# Preamp.net
KiCad netlist of a schematic drawn in Altium Designer
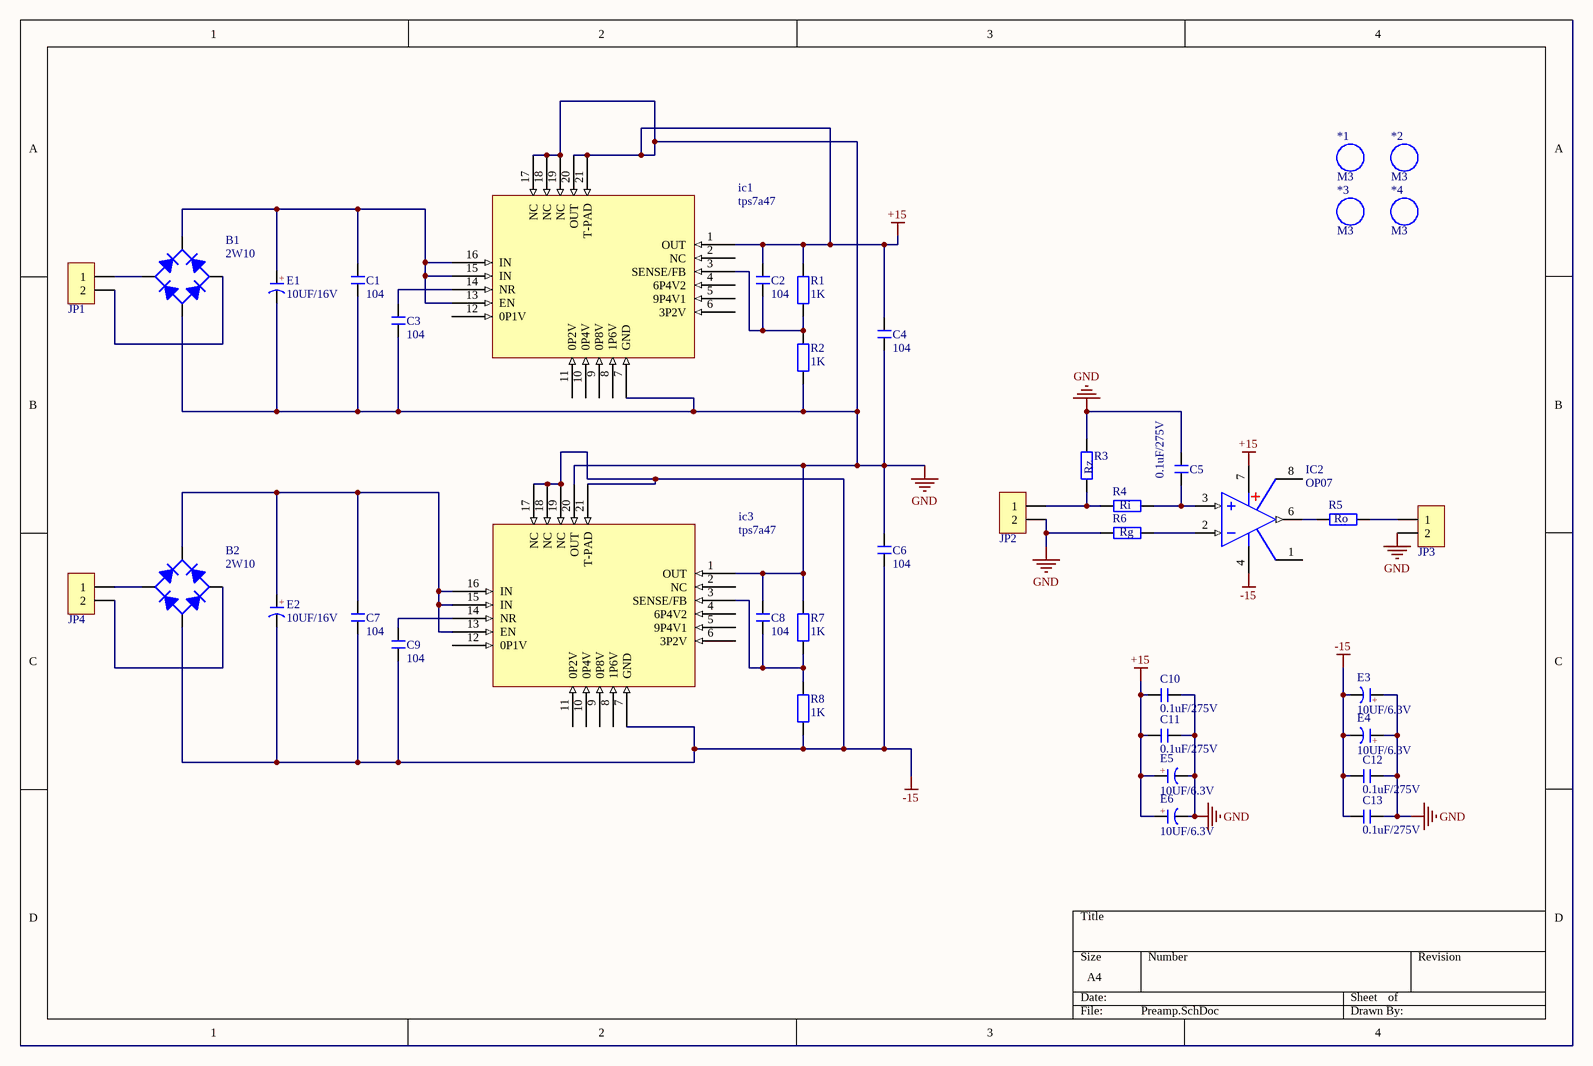
[diagram p0: Preamp.SchDoc]

(export (version "E")
  (design (tool "Eeschema 10.0.6"))
  (components
    (comp (ref "*1")
      (value "M3")
      (footprint "M3 125X300")
      (description "铜柱孔")
      (fields (field (name "版权归属") "源创客"))
      (libsource (lib "未分類") (part "M3"))
    )
    (comp (ref "*2")
      (value "M3")
      (footprint "M3 125X300")
      (description "铜柱孔")
      (fields (field (name "版权归属") "源创客"))
      (libsource (lib "未分類") (part "M3"))
    )
    (comp (ref "*3")
      (value "M3")
      (footprint "M3 125X300")
      (description "铜柱孔")
      (fields (field (name "版权归属") "源创客"))
      (libsource (lib "未分類") (part "M3"))
    )
    (comp (ref "*4")
      (value "M3")
      (footprint "M3 125X300")
      (description "铜柱孔")
      (fields (field (name "版权归属") "源创客"))
      (libsource (lib "未分類") (part "M3"))
    )
    (comp (ref "B1")
      (value "2W10")
      (footprint "RB-20")
      (description "1KV/2A淕霜")
      (libsource (lib "二極管-整流橋") (part "2W10"))
    )
    (comp (ref "B2")
      (value "2W10")
      (footprint "RB-20")
      (description "1KV/2A淕霜")
      (libsource (lib "二極管-整流橋") (part "2W10"))
    )
    (comp (ref "C1")
      (value "104")
      (footprint "C 0603")
      (description "拸憤俶泂萇")
      (libsource (lib "電阻-電容-電感") (part "C"))
    )
    (comp (ref "C2")
      (value "104")
      (footprint "C 0603")
      (description "拸憤俶泂萇")
      (libsource (lib "電阻-電容-電感") (part "C"))
    )
    (comp (ref "C3")
      (value "104")
      (footprint "C 0603")
      (description "拸憤俶泂萇")
      (libsource (lib "電阻-電容-電感") (part "C"))
    )
    (comp (ref "C4")
      (value "104")
      (footprint "C 0603")
      (description "拸憤俶泂萇")
      (libsource (lib "電阻-電容-電感") (part "C"))
    )
    (comp (ref "C5")
      (value "0.1uF/275V")
      (footprint "CBB-CL71")
      (description "CBB萇")
      (libsource (lib "電阻-電容-電感") (part "C-CBB"))
    )
    (comp (ref "C6")
      (value "104")
      (footprint "C 0603")
      (description "拸憤俶泂萇")
      (libsource (lib "電阻-電容-電感") (part "C"))
    )
    (comp (ref "C7")
      (value "104")
      (footprint "C 0603")
      (description "拸憤俶泂萇")
      (libsource (lib "電阻-電容-電感") (part "C"))
    )
    (comp (ref "C8")
      (value "104")
      (footprint "C 0603")
      (description "拸憤俶泂萇")
      (libsource (lib "電阻-電容-電感") (part "C"))
    )
    (comp (ref "C9")
      (value "104")
      (footprint "C 0603")
      (description "拸憤俶泂萇")
      (libsource (lib "電阻-電容-電感") (part "C"))
    )
    (comp (ref "C10")
      (value "0.1uF/275V")
      (footprint "CBB-CL71")
      (description "CBB萇")
      (libsource (lib "電阻-電容-電感") (part "C-CBB"))
    )
    (comp (ref "C11")
      (value "0.1uF/275V")
      (footprint "CBB-CL71")
      (description "CBB萇")
      (libsource (lib "電阻-電容-電感") (part "C-CBB"))
    )
    (comp (ref "C12")
      (value "0.1uF/275V")
      (footprint "CBB-CL71")
      (description "CBB萇")
      (libsource (lib "電阻-電容-電感") (part "C-CBB"))
    )
    (comp (ref "C13")
      (value "0.1uF/275V")
      (footprint "CBB-CL71")
      (description "CBB萇")
      (libsource (lib "電阻-電容-電感") (part "C-CBB"))
    )
    (comp (ref "E1")
      (value "10UF/16V")
      (footprint "CAP 7.5*18*35.5")
      (description "眻脣萇賤萇")
      (libsource (lib "電阻-電容-電感") (part "C-CAP"))
    )
    (comp (ref "E2")
      (value "10UF/16V")
      (footprint "CAP 7.5*18*35.5")
      (description "眻脣萇賤萇")
      (libsource (lib "電阻-電容-電感") (part "C-CAP"))
    )
    (comp (ref "E3")
      (value "10UF/6.3V")
      (footprint "CS 5.0*10*13 - C")
      (description "眻脣嘐怓萇")
      (libsource (lib "電阻-電容-電感") (part "C-CS"))
    )
    (comp (ref "E4")
      (value "10UF/6.3V")
      (footprint "CS 5.0*10*13 - C")
      (description "眻脣嘐怓萇")
      (libsource (lib "電阻-電容-電感") (part "C-CS"))
    )
    (comp (ref "E5")
      (value "10UF/6.3V")
      (footprint "CS 5.0*10*13 - C")
      (description "眻脣嘐怓萇")
      (libsource (lib "電阻-電容-電感") (part "C-CS"))
    )
    (comp (ref "E6")
      (value "10UF/6.3V")
      (footprint "CS 5.0*10*13 - C")
      (description "眻脣嘐怓萇")
      (libsource (lib "電阻-電容-電感") (part "C-CS"))
    )
    (comp (ref "ic1")
      (value "tps7a47")
      (footprint "QFN65P500X500X100_HS-21N")
      (description "TI RF LDO Voltage Regulator")
      (libsource (lib "vwvwbg") (part "tps7a47"))
    )
    (comp (ref "IC2")
      (value "OP07")
      (footprint "DIP8-300")
      (description "单路精密运放")
      (fields (field (name "版权归属") "源创客"))
      (libsource (lib "IC芯片") (part "OP07"))
    )
    (comp (ref "ic3")
      (value "tps7a47")
      (footprint "QFN65P500X500X100_HS-21N")
      (description "TI RF LDO Voltage Regulator")
      (libsource (lib "vwvwbg") (part "tps7a47"))
    )
    (comp (ref "JP1")
      (value "HDR-1X2")
      (footprint "KF2EDGK5.08-2P")
      (description "2P諉脣璃")
      (libsource (lib "") (part "Header 2_1"))
    )
    (comp (ref "JP2")
      (value "HDR-1X2")
      (footprint "KF2EDGK5.08-2P")
      (description "2P諉脣璃")
      (libsource (lib "") (part "Header 2_1"))
    )
    (comp (ref "JP3")
      (value "HDR-1X2")
      (footprint "KF2EDGK5.08-2P")
      (description "2P諉脣璃")
      (libsource (lib "接插件") (part "Header 2"))
    )
    (comp (ref "JP4")
      (value "HDR-1X2")
      (footprint "KF2EDGK5.08-2P")
      (description "2P諉脣璃")
      (libsource (lib "") (part "Header 2_1"))
    )
    (comp (ref "R1")
      (value "1K")
      (footprint "R 0805")
      (description "泂萇郯")
      (libsource (lib "電阻-電容-電感") (part "R"))
    )
    (comp (ref "R2")
      (value "1K")
      (footprint "R 0805")
      (description "泂萇郯")
      (libsource (lib "電阻-電容-電感") (part "R"))
    )
    (comp (ref "R3")
      (value "Rz")
      (footprint "RS 1/2W")
      (description "眻脣伎遠萇郯")
      (libsource (lib "電阻-電容-電感") (part "R-CRR"))
    )
    (comp (ref "R4")
      (value "Ri")
      (footprint "RS 1/2W")
      (description "眻脣伎遠萇郯")
      (libsource (lib "電阻-電容-電感") (part "R-CRR"))
    )
    (comp (ref "R5") (value "Ro") (footprint "RS 1/2W") (libsource (lib "電阻-電容-電感") (part "R-CRR")))
    (comp (ref "R6")
      (value "Rg")
      (footprint "RS 1/2W")
      (description "眻脣伎遠萇郯")
      (libsource (lib "電阻-電容-電感") (part "R-CRR"))
    )
    (comp (ref "R7")
      (value "1K")
      (footprint "R 0805")
      (description "泂萇郯")
      (libsource (lib "電阻-電容-電感") (part "R"))
    )
    (comp (ref "R8")
      (value "1K")
      (footprint "R 0805")
      (description "泂萇郯")
      (libsource (lib "電阻-電容-電感") (part "R"))
    )
  )
  (nets
    (net (code "1") (name "+15") (class "Default")
      (node (ref "B1") (pin "DC-") (pinfunction "DC-_DC-") (pintype "passive"))
      (node (ref "C1") (pin "1") (pinfunction "1_1") (pintype "passive"))
      (node (ref "C10") (pin "1") (pinfunction "1_1") (pintype "passive"))
      (node (ref "C10") (pin "2") (pinfunction "2_2") (pintype "passive"))
      (node (ref "C11") (pin "1") (pinfunction "1_1") (pintype "passive"))
      (node (ref "C11") (pin "2") (pinfunction "2_2") (pintype "passive"))
      (node (ref "C12") (pin "2") (pinfunction "2_2") (pintype "passive"))
      (node (ref "C13") (pin "2") (pinfunction "2_2") (pintype "passive"))
      (node (ref "C2") (pin "2") (pinfunction "2_2") (pintype "passive"))
      (node (ref "C3") (pin "1") (pinfunction "1_1") (pintype "passive"))
      (node (ref "C4") (pin "1") (pinfunction "1_1") (pintype "passive"))
      (node (ref "C4") (pin "2") (pinfunction "2_2") (pintype "passive"))
      (node (ref "C5") (pin "2") (pinfunction "2_2") (pintype "passive"))
      (node (ref "C6") (pin "2") (pinfunction "2_2") (pintype "passive"))
      (node (ref "C8") (pin "2") (pinfunction "2_2") (pintype "passive"))
      (node (ref "E1") (pin "2") (pinfunction "K_2") (pintype "passive"))
      (node (ref "E3") (pin "1") (pinfunction "A_1") (pintype "passive"))
      (node (ref "E4") (pin "1") (pinfunction "A_1") (pintype "passive"))
      (node (ref "E5") (pin "1") (pinfunction "A_1") (pintype "passive"))
      (node (ref "E5") (pin "2") (pinfunction "K_2") (pintype "passive"))
      (node (ref "E6") (pin "1") (pinfunction "A_1") (pintype "passive"))
      (node (ref "E6") (pin "2") (pinfunction "K_2") (pintype "passive"))
      (node (ref "IC2") (pin "7") (pinfunction "V+_7") (pintype "power_in"))
      (node (ref "JP2") (pin "2") (pinfunction "2_2") (pintype "passive"))
      (node (ref "JP3") (pin "2") (pinfunction "2_2") (pintype "passive"))
      (node (ref "R1") (pin "2") (pinfunction "2_2") (pintype "passive"))
      (node (ref "R2") (pin "1") (pinfunction "1_1") (pintype "passive"))
      (node (ref "R3") (pin "2") (pinfunction "2_2") (pintype "passive"))
      (node (ref "R6") (pin "1") (pinfunction "1_1") (pintype "passive"))
      (node (ref "R7") (pin "2") (pinfunction "2_2") (pintype "passive"))
      (node (ref "ic1") (pin "1") (pinfunction "OUT_1") (pintype "input"))
      (node (ref "ic1") (pin "17") (pinfunction "NC_17") (pintype "input"))
      (node (ref "ic1") (pin "18") (pinfunction "NC_18") (pintype "input"))
      (node (ref "ic1") (pin "19") (pinfunction "NC_19") (pintype "input"))
      (node (ref "ic1") (pin "20") (pinfunction "OUT_20") (pintype "input"))
      (node (ref "ic1") (pin "21") (pinfunction "T-PAD_21") (pintype "input"))
      (node (ref "ic1") (pin "7") (pinfunction "GND_7") (pintype "input"))
      (node (ref "ic3") (pin "1") (pinfunction "OUT_1") (pintype "input"))
      (node (ref "ic3") (pin "20") (pinfunction "OUT_20") (pintype "input"))
    )
    (net (code "2") (name "-15") (class "Default")
      (node (ref "B2") (pin "DC-") (pinfunction "DC-_DC-") (pintype "passive"))
      (node (ref "C12") (pin "1") (pinfunction "1_1") (pintype "passive"))
      (node (ref "C13") (pin "1") (pinfunction "1_1") (pintype "passive"))
      (node (ref "C6") (pin "1") (pinfunction "1_1") (pintype "passive"))
      (node (ref "C7") (pin "1") (pinfunction "1_1") (pintype "passive"))
      (node (ref "C9") (pin "1") (pinfunction "1_1") (pintype "passive"))
      (node (ref "E2") (pin "2") (pinfunction "K_2") (pintype "passive"))
      (node (ref "E3") (pin "2") (pinfunction "K_2") (pintype "passive"))
      (node (ref "E4") (pin "2") (pinfunction "K_2") (pintype "passive"))
      (node (ref "IC2") (pin "4") (pinfunction "V-_4") (pintype "power_in"))
      (node (ref "R8") (pin "1") (pinfunction "1_1") (pintype "passive"))
      (node (ref "ic3") (pin "17") (pinfunction "NC_17") (pintype "input"))
      (node (ref "ic3") (pin "18") (pinfunction "NC_18") (pintype "input"))
      (node (ref "ic3") (pin "19") (pinfunction "NC_19") (pintype "input"))
      (node (ref "ic3") (pin "21") (pinfunction "T-PAD_21") (pintype "input"))
      (node (ref "ic3") (pin "7") (pinfunction "GND_7") (pintype "input"))
    )
    (net (code "3") (name "Net-(B1-PadAC1)") (class "Default")
      (node (ref "B1") (pin "AC1") (pinfunction "AC1_AC1") (pintype "passive"))
      (node (ref "JP1") (pin "1") (pinfunction "1_1") (pintype "passive"))
    )
    (net (code "4") (name "Net-(B1-PadAC2)") (class "Default")
      (node (ref "B1") (pin "AC2") (pinfunction "AC2_AC2") (pintype "passive"))
      (node (ref "JP1") (pin "2") (pinfunction "2_2") (pintype "passive"))
    )
    (net (code "5") (name "Net-(B2-PadAC1)") (class "Default")
      (node (ref "B2") (pin "AC1") (pinfunction "AC1_AC1") (pintype "passive"))
      (node (ref "JP4") (pin "1") (pinfunction "1_1") (pintype "passive"))
    )
    (net (code "6") (name "Net-(B2-PadAC2)") (class "Default")
      (node (ref "B2") (pin "AC2") (pinfunction "AC2_AC2") (pintype "passive"))
      (node (ref "JP4") (pin "2") (pinfunction "2_2") (pintype "passive"))
    )
    (net (code "7") (name "Net-(E1-A)") (class "Default")
      (node (ref "B1") (pin "DC+") (pinfunction "DC+_DC+") (pintype "passive"))
      (node (ref "C1") (pin "2") (pinfunction "2_2") (pintype "passive"))
      (node (ref "E1") (pin "1") (pinfunction "A_1") (pintype "passive"))
      (node (ref "ic1") (pin "13") (pinfunction "EN_13") (pintype "input"))
      (node (ref "ic1") (pin "15") (pinfunction "IN_15") (pintype "input"))
      (node (ref "ic1") (pin "16") (pinfunction "IN_16") (pintype "input"))
    )
    (net (code "8") (name "Net-(E2-A)") (class "Default")
      (node (ref "B2") (pin "DC+") (pinfunction "DC+_DC+") (pintype "passive"))
      (node (ref "C7") (pin "2") (pinfunction "2_2") (pintype "passive"))
      (node (ref "E2") (pin "1") (pinfunction "A_1") (pintype "passive"))
      (node (ref "ic3") (pin "13") (pinfunction "EN_13") (pintype "input"))
      (node (ref "ic3") (pin "15") (pinfunction "IN_15") (pintype "input"))
      (node (ref "ic3") (pin "16") (pinfunction "IN_16") (pintype "input"))
    )
    (net (code "9") (name "Net-(IC2-IN+)") (class "Default")
      (node (ref "C5") (pin "1") (pinfunction "1_1") (pintype "passive"))
      (node (ref "IC2") (pin "3") (pinfunction "IN+_3") (pintype "input"))
      (node (ref "R4") (pin "2") (pinfunction "2_2") (pintype "passive"))
    )
    (net (code "10") (name "Net-(IC2-IN-)") (class "Default")
      (node (ref "IC2") (pin "2") (pinfunction "IN-_2") (pintype "input"))
      (node (ref "R6") (pin "2") (pinfunction "2_2") (pintype "passive"))
    )
    (net (code "11") (name "Net-(IC2-OUT)") (class "Default")
      (node (ref "IC2") (pin "6") (pinfunction "OUT_6") (pintype "output"))
      (node (ref "R5") (pin "1") (pinfunction "1_1") (pintype "passive"))
    )
    (net (code "12") (name "Net-(JP2-Pad1)") (class "Default")
      (node (ref "JP2") (pin "1") (pinfunction "1_1") (pintype "passive"))
      (node (ref "R3") (pin "1") (pinfunction "1_1") (pintype "passive"))
      (node (ref "R4") (pin "1") (pinfunction "1_1") (pintype "passive"))
    )
    (net (code "13") (name "Net-(JP3-Pad1)") (class "Default")
      (node (ref "JP3") (pin "1") (pinfunction "1_1") (pintype "passive"))
      (node (ref "R5") (pin "2") (pinfunction "2_2") (pintype "passive"))
    )
    (net (code "14") (name "Net-(ic1-NR)") (class "Default")
      (node (ref "C3") (pin "2") (pinfunction "2_2") (pintype "passive"))
      (node (ref "ic1") (pin "14") (pinfunction "NR_14") (pintype "input"))
    )
    (net (code "15") (name "Net-(ic1-SENSE{slash}FB)") (class "Default")
      (node (ref "C2") (pin "1") (pinfunction "1_1") (pintype "passive"))
      (node (ref "R1") (pin "1") (pinfunction "1_1") (pintype "passive"))
      (node (ref "R2") (pin "2") (pinfunction "2_2") (pintype "passive"))
      (node (ref "ic1") (pin "3") (pinfunction "SENSE/FB_3") (pintype "input"))
    )
    (net (code "16") (name "Net-(ic3-NR)") (class "Default")
      (node (ref "C9") (pin "2") (pinfunction "2_2") (pintype "passive"))
      (node (ref "ic3") (pin "14") (pinfunction "NR_14") (pintype "input"))
    )
    (net (code "17") (name "Net-(ic3-SENSE{slash}FB)") (class "Default")
      (node (ref "C8") (pin "1") (pinfunction "1_1") (pintype "passive"))
      (node (ref "R7") (pin "1") (pinfunction "1_1") (pintype "passive"))
      (node (ref "R8") (pin "2") (pinfunction "2_2") (pintype "passive"))
      (node (ref "ic3") (pin "3") (pinfunction "SENSE/FB_3") (pintype "input"))
    )
    (net (code "18") (name "unconnected-(IC2-Pad1)") (class "Default")
      (node (ref "IC2") (pin "1") (pinfunction "1_1") (pintype "passive"))
    )
    (net (code "19") (name "unconnected-(IC2-Pad8)") (class "Default")
      (node (ref "IC2") (pin "8") (pinfunction "8_8") (pintype "passive"))
    )
    (net (code "20") (name "unconnected-(ic1-0P1V-Pad12)") (class "Default")
      (node (ref "ic1") (pin "12") (pinfunction "0P1V_12") (pintype "input"))
    )
    (net (code "21") (name "unconnected-(ic1-0P2V-Pad11)") (class "Default")
      (node (ref "ic1") (pin "11") (pinfunction "0P2V_11") (pintype "input"))
    )
    (net (code "22") (name "unconnected-(ic1-0P4V-Pad10)") (class "Default")
      (node (ref "ic1") (pin "10") (pinfunction "0P4V_10") (pintype "input"))
    )
    (net (code "23") (name "unconnected-(ic1-0P8V-Pad9)") (class "Default")
      (node (ref "ic1") (pin "9") (pinfunction "0P8V_9") (pintype "input"))
    )
    (net (code "24") (name "unconnected-(ic1-1P6V-Pad8)") (class "Default")
      (node (ref "ic1") (pin "8") (pinfunction "1P6V_8") (pintype "input"))
    )
    (net (code "25") (name "unconnected-(ic1-3P2V-Pad6)") (class "Default")
      (node (ref "ic1") (pin "6") (pinfunction "3P2V_6") (pintype "input"))
    )
    (net (code "26") (name "unconnected-(ic1-6P4V2-Pad4)") (class "Default")
      (node (ref "ic1") (pin "4") (pinfunction "6P4V2_4") (pintype "input"))
    )
    (net (code "27") (name "unconnected-(ic1-9P4V1-Pad5)") (class "Default")
      (node (ref "ic1") (pin "5") (pinfunction "9P4V1_5") (pintype "input"))
    )
    (net (code "28") (name "unconnected-(ic1-NC-Pad2)") (class "Default")
      (node (ref "ic1") (pin "2") (pinfunction "NC_2") (pintype "input"))
    )
    (net (code "29") (name "unconnected-(ic3-0P1V-Pad12)") (class "Default")
      (node (ref "ic3") (pin "12") (pinfunction "0P1V_12") (pintype "input"))
    )
    (net (code "30") (name "unconnected-(ic3-0P2V-Pad11)") (class "Default")
      (node (ref "ic3") (pin "11") (pinfunction "0P2V_11") (pintype "input"))
    )
    (net (code "31") (name "unconnected-(ic3-0P4V-Pad10)") (class "Default")
      (node (ref "ic3") (pin "10") (pinfunction "0P4V_10") (pintype "input"))
    )
    (net (code "32") (name "unconnected-(ic3-0P8V-Pad9)") (class "Default")
      (node (ref "ic3") (pin "9") (pinfunction "0P8V_9") (pintype "input"))
    )
    (net (code "33") (name "unconnected-(ic3-1P6V-Pad8)") (class "Default")
      (node (ref "ic3") (pin "8") (pinfunction "1P6V_8") (pintype "input"))
    )
    (net (code "34") (name "unconnected-(ic3-3P2V-Pad6)") (class "Default")
      (node (ref "ic3") (pin "6") (pinfunction "3P2V_6") (pintype "input"))
    )
    (net (code "35") (name "unconnected-(ic3-6P4V2-Pad4)") (class "Default")
      (node (ref "ic3") (pin "4") (pinfunction "6P4V2_4") (pintype "input"))
    )
    (net (code "36") (name "unconnected-(ic3-9P4V1-Pad5)") (class "Default")
      (node (ref "ic3") (pin "5") (pinfunction "9P4V1_5") (pintype "input"))
    )
    (net (code "37") (name "unconnected-(ic3-NC-Pad2)") (class "Default")
      (node (ref "ic3") (pin "2") (pinfunction "NC_2") (pintype "input"))
    )
  )
)
